# SIM900A.net
KiCad netlist of a schematic drawn in Altium Designer
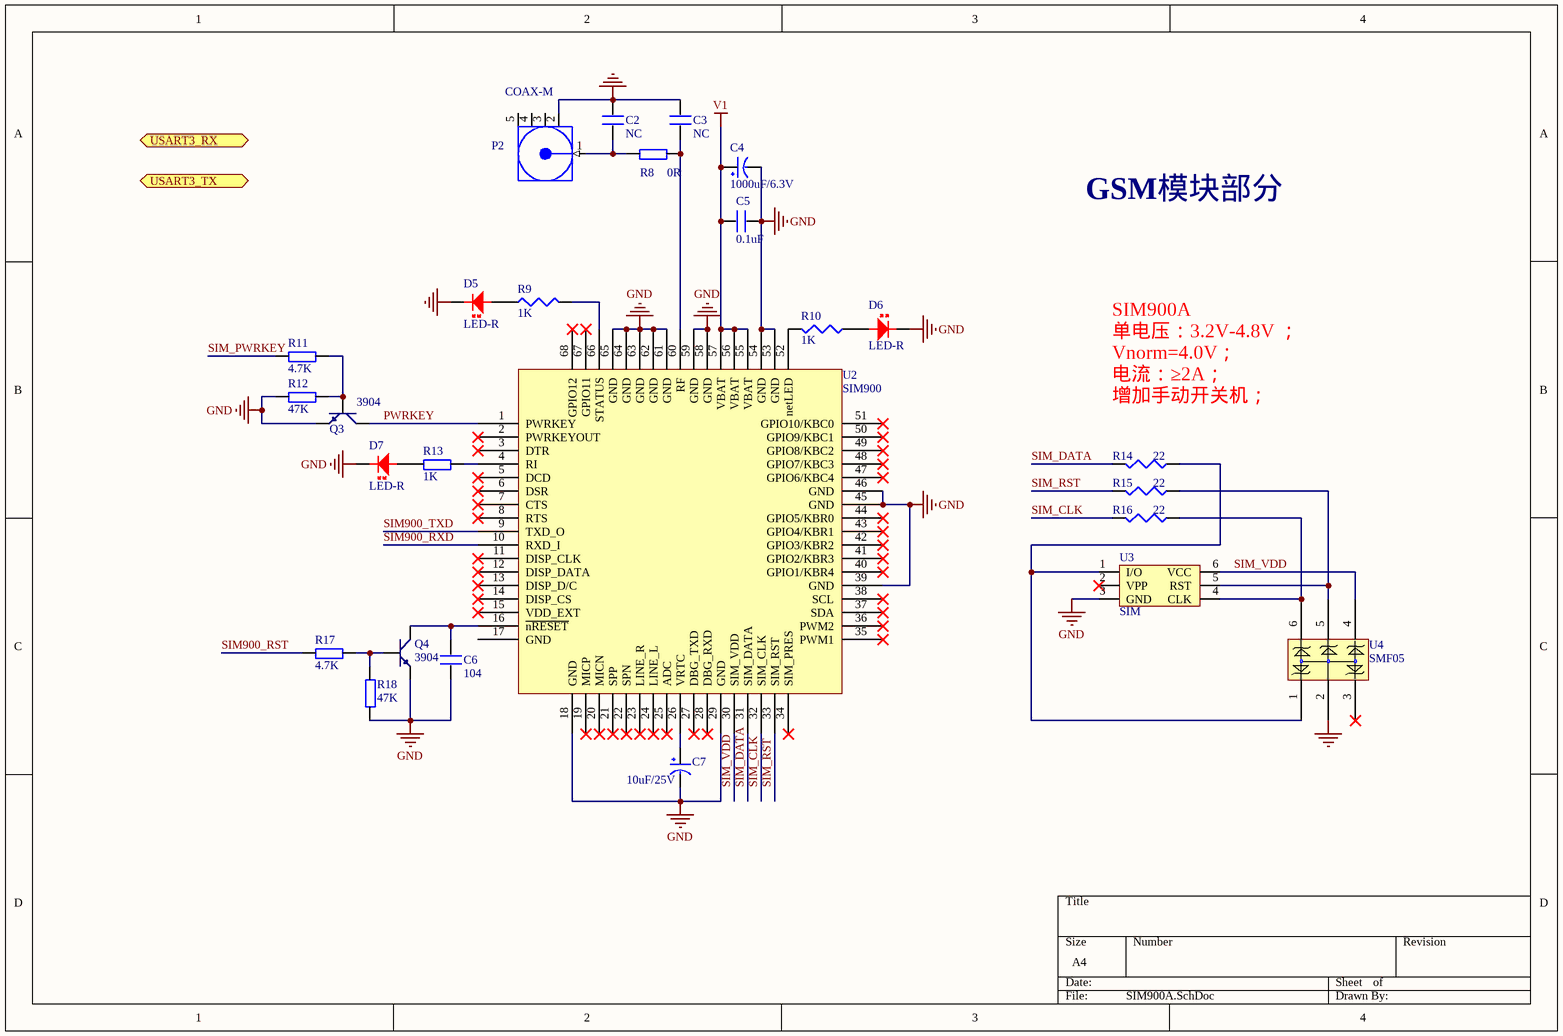
[diagram p0: SIM900A.SchDoc]

(export (version "E")
  (design (tool "Eeschema 10.0.6"))
  (components
    (comp (ref "C2") (value "NC") (footprint "0805") (libsource (lib "mylib") (part "C")))
    (comp (ref "C3") (value "NC") (footprint "0805") (libsource (lib "mylib") (part "C")))
    (comp (ref "C4") (value "1000uF/6.3V") (footprint "7343") (libsource (lib "mylib") (part "CAP")))
    (comp (ref "C5") (value "0.1uF") (footprint "0805") (libsource (lib "mylib") (part "C")))
    (comp (ref "C6") (value "104") (footprint "0805") (libsource (lib "mylib") (part "C")))
    (comp (ref "C7") (value "10uF/25V") (footprint "1206") (libsource (lib "") (part "CAP_1")))
    (comp (ref "D5")
      (value "LED-R")
      (footprint "LED-DIP")
      (description "红色LED")
      (libsource (lib "mylib") (part "LED-RED"))
    )
    (comp (ref "D6")
      (value "LED-R")
      (footprint "LED-DIP")
      (description "红色LED")
      (libsource (lib "mylib") (part "LED-RED"))
    )
    (comp (ref "D7")
      (value "LED-R")
      (footprint "LED-DIP")
      (description "红色LED")
      (libsource (lib "mylib") (part "LED-RED"))
    )
    (comp (ref "P2")
      (value "COAX-M")
      (footprint "ST-TH1")
      (description "SMA-J-P-H-ST-TH1")
      (fields (field (name "PUBLISHER") "Altium Limited"))
      (libsource (lib "Miscellaneous Connectors") (part "COAX-M"))
    )
    (comp (ref "Q3")
      (value "3904")
      (footprint "SOT-23R")
      (description "8050/BCW846/BCW847")
      (libsource (lib "mylib") (part "NPN"))
    )
    (comp (ref "Q4")
      (value "3904")
      (footprint "SOT-23R")
      (description "8050/BCW846/BCW847")
      (libsource (lib "mylib") (part "NPN"))
    )
    (comp (ref "R8") (value "0R") (footprint "0603") (libsource (lib "mylib") (part "Res")))
    (comp (ref "R9") (value "1K") (footprint "0805") (libsource (lib "INSPUR_SCH") (part "RES1")))
    (comp (ref "R10") (value "1K") (footprint "0805") (libsource (lib "INSPUR_SCH") (part "RES1")))
    (comp (ref "R11") (value "4.7K") (footprint "0805") (libsource (lib "mylib") (part "Res")))
    (comp (ref "R12") (value "47K") (footprint "0805") (libsource (lib "mylib") (part "Res")))
    (comp (ref "R13") (value "1K") (footprint "0805") (libsource (lib "mylib") (part "Res")))
    (comp (ref "R14") (value "22") (footprint "0805") (libsource (lib "INSPUR_SCH") (part "RES1")))
    (comp (ref "R15") (value "22") (footprint "0805") (libsource (lib "INSPUR_SCH") (part "RES1")))
    (comp (ref "R16") (value "22") (footprint "0805") (libsource (lib "INSPUR_SCH") (part "RES1")))
    (comp (ref "R17") (value "4.7K") (footprint "0805") (libsource (lib "mylib") (part "Res")))
    (comp (ref "R18") (value "47K") (footprint "0805") (libsource (lib "mylib") (part "Res")))
    (comp (ref "U2") (value "SIM900") (footprint "SIM-900") (libsource (lib "ATK-SIM900A") (part "SIM900")))
    (comp (ref "U3")
      (value "SIM")
      (footprint "sim-6p")
      (description "手机SIM卡")
      (libsource (lib "ATK-SIM900A") (part "SIM"))
    )
    (comp (ref "U4") (value "SMF05") (footprint "SC70-6L") (libsource (lib "INSPUR_SCH") (part "SMF05")))
  )
  (nets
    (net (code "1") (name "/PWRKEY") (class "Default")
      (node (ref "Q3") (pin "3") (pinfunction "C_3") (pintype "passive"))
      (node (ref "U2") (pin "1") (pinfunction "PWRKEY_1") (pintype "passive"))
    )
    (net (code "2") (name "/SIM900_RST") (class "Default") (node (ref "R17") (pin "1") (pintype "passive")))
    (net (code "3") (name "/SIM900_RXD") (class "Default")
      (node (ref "U2") (pin "10") (pinfunction "RXD_I_10") (pintype "passive"))
    )
    (net (code "4") (name "/SIM900_TXD") (class "Default")
      (node (ref "U2") (pin "9") (pinfunction "TXD_O_9") (pintype "passive"))
    )
    (net (code "5") (name "/SIM_CLK") (class "Default")
      (node (ref "R16") (pin "2") (pinfunction "2_2") (pintype "passive"))
      (node (ref "U2") (pin "32") (pinfunction "SIM_CLK_32") (pintype "passive"))
    )
    (net (code "6") (name "/SIM_DATA") (class "Default")
      (node (ref "R14") (pin "2") (pinfunction "2_2") (pintype "passive"))
      (node (ref "U2") (pin "31") (pinfunction "SIM_DATA_31") (pintype "passive"))
    )
    (net (code "7") (name "/SIM_PWRKEY") (class "Default") (node (ref "R11") (pin "1") (pintype "passive")))
    (net (code "8") (name "/SIM_RST") (class "Default")
      (node (ref "R15") (pin "2") (pinfunction "2_2") (pintype "passive"))
      (node (ref "U2") (pin "33") (pinfunction "SIM_RST_33") (pintype "passive"))
    )
    (net (code "9") (name "/SIM_VDD") (class "Default")
      (node (ref "U2") (pin "30") (pinfunction "SIM_VDD_30") (pintype "passive"))
      (node (ref "U3") (pin "6") (pinfunction "VCC_6") (pintype "passive"))
      (node (ref "U4") (pin "4") (pintype "passive"))
    )
    (net (code "12") (name "GND") (class "Default")
      (node (ref "C2") (pin "2") (pintype "passive"))
      (node (ref "C3") (pin "2") (pintype "passive"))
      (node (ref "C4") (pin "2") (pinfunction "GND_2") (pintype "passive"))
      (node (ref "C5") (pin "2") (pintype "passive"))
      (node (ref "C6") (pin "1") (pintype "passive"))
      (node (ref "C7") (pin "2") (pinfunction "GND_2") (pintype "passive"))
      (node (ref "D5") (pin "2") (pintype "passive"))
      (node (ref "D6") (pin "2") (pintype "passive"))
      (node (ref "D7") (pin "2") (pintype "passive"))
      (node (ref "P2") (pin "2") (pinfunction "GND_2") (pintype "power_in"))
      (node (ref "Q3") (pin "1") (pinfunction "E_1") (pintype "passive"))
      (node (ref "Q4") (pin "1") (pinfunction "E_1") (pintype "passive"))
      (node (ref "R12") (pin "1") (pintype "passive"))
      (node (ref "R18") (pin "1") (pintype "passive"))
      (node (ref "U2") (pin "18") (pinfunction "GND_18") (pintype "passive"))
      (node (ref "U2") (pin "29") (pinfunction "GND_29") (pintype "passive"))
      (node (ref "U2") (pin "39") (pinfunction "GND_39") (pintype "passive"))
      (node (ref "U2") (pin "45") (pinfunction "GND_45") (pintype "passive"))
      (node (ref "U2") (pin "46") (pinfunction "GND_46") (pintype "passive"))
      (node (ref "U2") (pin "53") (pinfunction "GND_53") (pintype "passive"))
      (node (ref "U2") (pin "54") (pinfunction "GND_54") (pintype "passive"))
      (node (ref "U2") (pin "58") (pinfunction "GND_58") (pintype "passive"))
      (node (ref "U2") (pin "59") (pinfunction "GND_59") (pintype "passive"))
      (node (ref "U2") (pin "61") (pinfunction "GND_61") (pintype "passive"))
      (node (ref "U2") (pin "62") (pinfunction "GND_62") (pintype "passive"))
      (node (ref "U2") (pin "63") (pinfunction "GND_63") (pintype "passive"))
      (node (ref "U2") (pin "64") (pinfunction "GND_64") (pintype "passive"))
      (node (ref "U2") (pin "65") (pinfunction "GND_65") (pintype "passive"))
      (node (ref "U3") (pin "3") (pinfunction "GND_3") (pintype "passive"))
      (node (ref "U4") (pin "2") (pintype "passive"))
    )
    (net (code "13") (name "Net-(C7-VCC)") (class "Default")
      (node (ref "C7") (pin "1") (pinfunction "VCC_1") (pintype "passive"))
      (node (ref "U2") (pin "26") (pinfunction "VRTC_26") (pintype "passive"))
    )
    (net (code "14") (name "Net-(D5-Pad1)") (class "Default")
      (node (ref "D5") (pin "1") (pintype "passive"))
      (node (ref "R9") (pin "1") (pinfunction "1_1") (pintype "passive"))
    )
    (net (code "15") (name "Net-(D6-Pad1)") (class "Default")
      (node (ref "D6") (pin "1") (pintype "passive"))
      (node (ref "R10") (pin "1") (pinfunction "1_1") (pintype "passive"))
    )
    (net (code "16") (name "Net-(D7-Pad1)") (class "Default")
      (node (ref "D7") (pin "1") (pintype "passive"))
      (node (ref "R13") (pin "1") (pintype "passive"))
    )
    (net (code "17") (name "Net-(P2-Signal)") (class "Default")
      (node (ref "C2") (pin "1") (pintype "passive"))
      (node (ref "P2") (pin "1") (pinfunction "Signal_1") (pintype "input"))
      (node (ref "R8") (pin "1") (pintype "passive"))
    )
    (net (code "18") (name "Net-(Q3-B)") (class "Default")
      (node (ref "Q3") (pin "2") (pinfunction "B_2") (pintype "passive"))
      (node (ref "R11") (pin "2") (pintype "passive"))
      (node (ref "R12") (pin "2") (pintype "passive"))
    )
    (net (code "19") (name "Net-(Q4-B)") (class "Default")
      (node (ref "Q4") (pin "2") (pinfunction "B_2") (pintype "passive"))
      (node (ref "R17") (pin "2") (pintype "passive"))
      (node (ref "R18") (pin "2") (pintype "passive"))
    )
    (net (code "20") (name "Net-(Q4-C)") (class "Default")
      (node (ref "C6") (pin "2") (pintype "passive"))
      (node (ref "Q4") (pin "3") (pinfunction "C_3") (pintype "passive"))
      (node (ref "U2") (pin "16") (pinfunction "~{nRESET}_16") (pintype "passive"))
    )
    (net (code "21") (name "Net-(U2-RF)") (class "Default")
      (node (ref "C3") (pin "1") (pintype "passive"))
      (node (ref "R8") (pin "2") (pintype "passive"))
      (node (ref "U2") (pin "60") (pinfunction "RF_60") (pintype "passive"))
    )
    (net (code "22") (name "Net-(U2-RI)") (class "Default")
      (node (ref "R13") (pin "2") (pintype "passive"))
      (node (ref "U2") (pin "4") (pinfunction "RI_4") (pintype "passive"))
    )
    (net (code "23") (name "Net-(U2-STATUS)") (class "Default")
      (node (ref "R9") (pin "2") (pinfunction "2_2") (pintype "passive"))
      (node (ref "U2") (pin "66") (pinfunction "STATUS_66") (pintype "passive"))
    )
    (net (code "24") (name "Net-(U2-netLED)") (class "Default")
      (node (ref "R10") (pin "2") (pinfunction "2_2") (pintype "passive"))
      (node (ref "U2") (pin "52") (pinfunction "netLED_52") (pintype "passive"))
    )
    (net (code "25") (name "Net-(U3-CLK)") (class "Default")
      (node (ref "R16") (pin "1") (pinfunction "1_1") (pintype "passive"))
      (node (ref "U3") (pin "4") (pinfunction "CLK_4") (pintype "passive"))
      (node (ref "U4") (pin "6") (pintype "passive"))
    )
    (net (code "26") (name "Net-(U3-I{slash}O)") (class "Default")
      (node (ref "R14") (pin "1") (pinfunction "1_1") (pintype "passive"))
      (node (ref "U3") (pin "1") (pinfunction "I/O_1") (pintype "passive"))
      (node (ref "U4") (pin "1") (pintype "passive"))
    )
    (net (code "27") (name "Net-(U3-RST)") (class "Default")
      (node (ref "R15") (pin "1") (pinfunction "1_1") (pintype "passive"))
      (node (ref "U3") (pin "5") (pinfunction "RST_5") (pintype "passive"))
      (node (ref "U4") (pin "5") (pintype "passive"))
    )
    (net (code "28") (name "V1") (class "Default")
      (node (ref "C4") (pin "1") (pinfunction "VCC_1") (pintype "passive"))
      (node (ref "C5") (pin "1") (pintype "passive"))
      (node (ref "U2") (pin "55") (pinfunction "VBAT_55") (pintype "passive"))
      (node (ref "U2") (pin "56") (pinfunction "VBAT_56") (pintype "passive"))
      (node (ref "U2") (pin "57") (pinfunction "VBAT_57") (pintype "passive"))
    )
    (net (code "29") (name "unconnected-(P2-GND-Pad3)") (class "Default")
      (node (ref "P2") (pin "3") (pinfunction "GND_3") (pintype "power_in"))
    )
    (net (code "30") (name "unconnected-(P2-GND-Pad4)") (class "Default")
      (node (ref "P2") (pin "4") (pinfunction "GND_4") (pintype "power_in"))
    )
    (net (code "31") (name "unconnected-(P2-GND-Pad5)") (class "Default")
      (node (ref "P2") (pin "5") (pinfunction "GND_5") (pintype "power_in"))
    )
    (net (code "32") (name "unconnected-(U2-ADC-Pad25)") (class "Default")
      (node (ref "U2") (pin "25") (pinfunction "ADC_25") (pintype "passive+no_connect"))
    )
    (net (code "33") (name "unconnected-(U2-CTS-Pad7)") (class "Default")
      (node (ref "U2") (pin "7") (pinfunction "CTS_7") (pintype "passive+no_connect"))
    )
    (net (code "34") (name "unconnected-(U2-DBG_RXD-Pad28)") (class "Default")
      (node (ref "U2") (pin "28") (pinfunction "DBG_RXD_28") (pintype "passive+no_connect"))
    )
    (net (code "35") (name "unconnected-(U2-DBG_TXD-Pad27)") (class "Default")
      (node (ref "U2") (pin "27") (pinfunction "DBG_TXD_27") (pintype "passive+no_connect"))
    )
    (net (code "36") (name "unconnected-(U2-DCD-Pad5)") (class "Default")
      (node (ref "U2") (pin "5") (pinfunction "DCD_5") (pintype "passive+no_connect"))
    )
    (net (code "37") (name "unconnected-(U2-DISP_CLK-Pad11)") (class "Default")
      (node (ref "U2") (pin "11") (pinfunction "DISP_CLK_11") (pintype "passive+no_connect"))
    )
    (net (code "38") (name "unconnected-(U2-DISP_CS-Pad14)") (class "Default")
      (node (ref "U2") (pin "14") (pinfunction "DISP_CS_14") (pintype "passive+no_connect"))
    )
    (net (code "39") (name "unconnected-(U2-DISP_DATA-Pad12)") (class "Default")
      (node (ref "U2") (pin "12") (pinfunction "DISP_DATA_12") (pintype "passive+no_connect"))
    )
    (net (code "40") (name "unconnected-(U2-DISP_D{slash}C-Pad13)") (class "Default")
      (node (ref "U2") (pin "13") (pinfunction "DISP_D/C_13") (pintype "passive+no_connect"))
    )
    (net (code "41") (name "unconnected-(U2-DSR-Pad6)") (class "Default")
      (node (ref "U2") (pin "6") (pinfunction "DSR_6") (pintype "passive+no_connect"))
    )
    (net (code "42") (name "unconnected-(U2-DTR-Pad3)") (class "Default")
      (node (ref "U2") (pin "3") (pinfunction "DTR_3") (pintype "passive+no_connect"))
    )
    (net (code "43") (name "unconnected-(U2-GND-Pad17)") (class "Default")
      (node (ref "U2") (pin "17") (pinfunction "GND_17") (pintype "passive"))
    )
    (net (code "44") (name "unconnected-(U2-GPIO1{slash}KBR4-Pad40)") (class "Default")
      (node (ref "U2") (pin "40") (pinfunction "GPIO1/KBR4_40") (pintype "passive+no_connect"))
    )
    (net (code "45") (name "unconnected-(U2-GPIO2{slash}KBR3-Pad41)") (class "Default")
      (node (ref "U2") (pin "41") (pinfunction "GPIO2/KBR3_41") (pintype "passive+no_connect"))
    )
    (net (code "46") (name "unconnected-(U2-GPIO3{slash}KBR2-Pad42)") (class "Default")
      (node (ref "U2") (pin "42") (pinfunction "GPIO3/KBR2_42") (pintype "passive+no_connect"))
    )
    (net (code "47") (name "unconnected-(U2-GPIO4{slash}KBR1-Pad43)") (class "Default")
      (node (ref "U2") (pin "43") (pinfunction "GPIO4/KBR1_43") (pintype "passive+no_connect"))
    )
    (net (code "48") (name "unconnected-(U2-GPIO5{slash}KBR0-Pad44)") (class "Default")
      (node (ref "U2") (pin "44") (pinfunction "GPIO5/KBR0_44") (pintype "passive+no_connect"))
    )
    (net (code "49") (name "unconnected-(U2-GPIO6{slash}KBC4-Pad47)") (class "Default")
      (node (ref "U2") (pin "47") (pinfunction "GPIO6/KBC4_47") (pintype "passive+no_connect"))
    )
    (net (code "50") (name "unconnected-(U2-GPIO7{slash}KBC3-Pad48)") (class "Default")
      (node (ref "U2") (pin "48") (pinfunction "GPIO7/KBC3_48") (pintype "passive+no_connect"))
    )
    (net (code "51") (name "unconnected-(U2-GPIO8{slash}KBC2-Pad49)") (class "Default")
      (node (ref "U2") (pin "49") (pinfunction "GPIO8/KBC2_49") (pintype "passive+no_connect"))
    )
    (net (code "52") (name "unconnected-(U2-GPIO9{slash}KBC1-Pad50)") (class "Default")
      (node (ref "U2") (pin "50") (pinfunction "GPIO9/KBC1_50") (pintype "passive+no_connect"))
    )
    (net (code "53") (name "unconnected-(U2-GPIO10{slash}KBC0-Pad51)") (class "Default")
      (node (ref "U2") (pin "51") (pinfunction "GPIO10/KBC0_51") (pintype "passive+no_connect"))
    )
    (net (code "54") (name "unconnected-(U2-GPIO11-Pad67)") (class "Default")
      (node (ref "U2") (pin "67") (pinfunction "GPIO11_67") (pintype "passive+no_connect"))
    )
    (net (code "55") (name "unconnected-(U2-GPIO12-Pad68)") (class "Default")
      (node (ref "U2") (pin "68") (pinfunction "GPIO12_68") (pintype "passive+no_connect"))
    )
    (net (code "56") (name "unconnected-(U2-LINE_L-Pad24)") (class "Default")
      (node (ref "U2") (pin "24") (pinfunction "LINE_L_24") (pintype "passive+no_connect"))
    )
    (net (code "57") (name "unconnected-(U2-LINE_R-Pad23)") (class "Default")
      (node (ref "U2") (pin "23") (pinfunction "LINE_R_23") (pintype "passive+no_connect"))
    )
    (net (code "58") (name "unconnected-(U2-MICN-Pad20)") (class "Default")
      (node (ref "U2") (pin "20") (pinfunction "MICN_20") (pintype "passive+no_connect"))
    )
    (net (code "59") (name "unconnected-(U2-MICP-Pad19)") (class "Default")
      (node (ref "U2") (pin "19") (pinfunction "MICP_19") (pintype "passive+no_connect"))
    )
    (net (code "60") (name "unconnected-(U2-PWM1-Pad35)") (class "Default")
      (node (ref "U2") (pin "35") (pinfunction "PWM1_35") (pintype "passive+no_connect"))
    )
    (net (code "61") (name "unconnected-(U2-PWM2-Pad36)") (class "Default")
      (node (ref "U2") (pin "36") (pinfunction "PWM2_36") (pintype "passive+no_connect"))
    )
    (net (code "62") (name "unconnected-(U2-PWRKEYOUT-Pad2)") (class "Default")
      (node (ref "U2") (pin "2") (pinfunction "PWRKEYOUT_2") (pintype "passive+no_connect"))
    )
    (net (code "63") (name "unconnected-(U2-RTS-Pad8)") (class "Default")
      (node (ref "U2") (pin "8") (pinfunction "RTS_8") (pintype "passive+no_connect"))
    )
    (net (code "64") (name "unconnected-(U2-SCL-Pad38)") (class "Default")
      (node (ref "U2") (pin "38") (pinfunction "SCL_38") (pintype "passive+no_connect"))
    )
    (net (code "65") (name "unconnected-(U2-SDA-Pad37)") (class "Default")
      (node (ref "U2") (pin "37") (pinfunction "SDA_37") (pintype "passive+no_connect"))
    )
    (net (code "66") (name "unconnected-(U2-SIM_PRES-Pad34)") (class "Default")
      (node (ref "U2") (pin "34") (pinfunction "SIM_PRES_34") (pintype "passive+no_connect"))
    )
    (net (code "67") (name "unconnected-(U2-SPN-Pad22)") (class "Default")
      (node (ref "U2") (pin "22") (pinfunction "SPN_22") (pintype "passive+no_connect"))
    )
    (net (code "68") (name "unconnected-(U2-SPP-Pad21)") (class "Default")
      (node (ref "U2") (pin "21") (pinfunction "SPP_21") (pintype "passive+no_connect"))
    )
    (net (code "69") (name "unconnected-(U2-VDD_EXT-Pad15)") (class "Default")
      (node (ref "U2") (pin "15") (pinfunction "VDD_EXT_15") (pintype "passive+no_connect"))
    )
    (net (code "70") (name "unconnected-(U3-VPP-Pad2)") (class "Default")
      (node (ref "U3") (pin "2") (pinfunction "VPP_2") (pintype "passive+no_connect"))
    )
    (net (code "71") (name "unconnected-(U4-Pad3)") (class "Default")
      (node (ref "U4") (pin "3") (pintype "passive+no_connect"))
    )
  )
)
